# Sheet1.net
KiCad netlist of a schematic drawn in Altium Designer
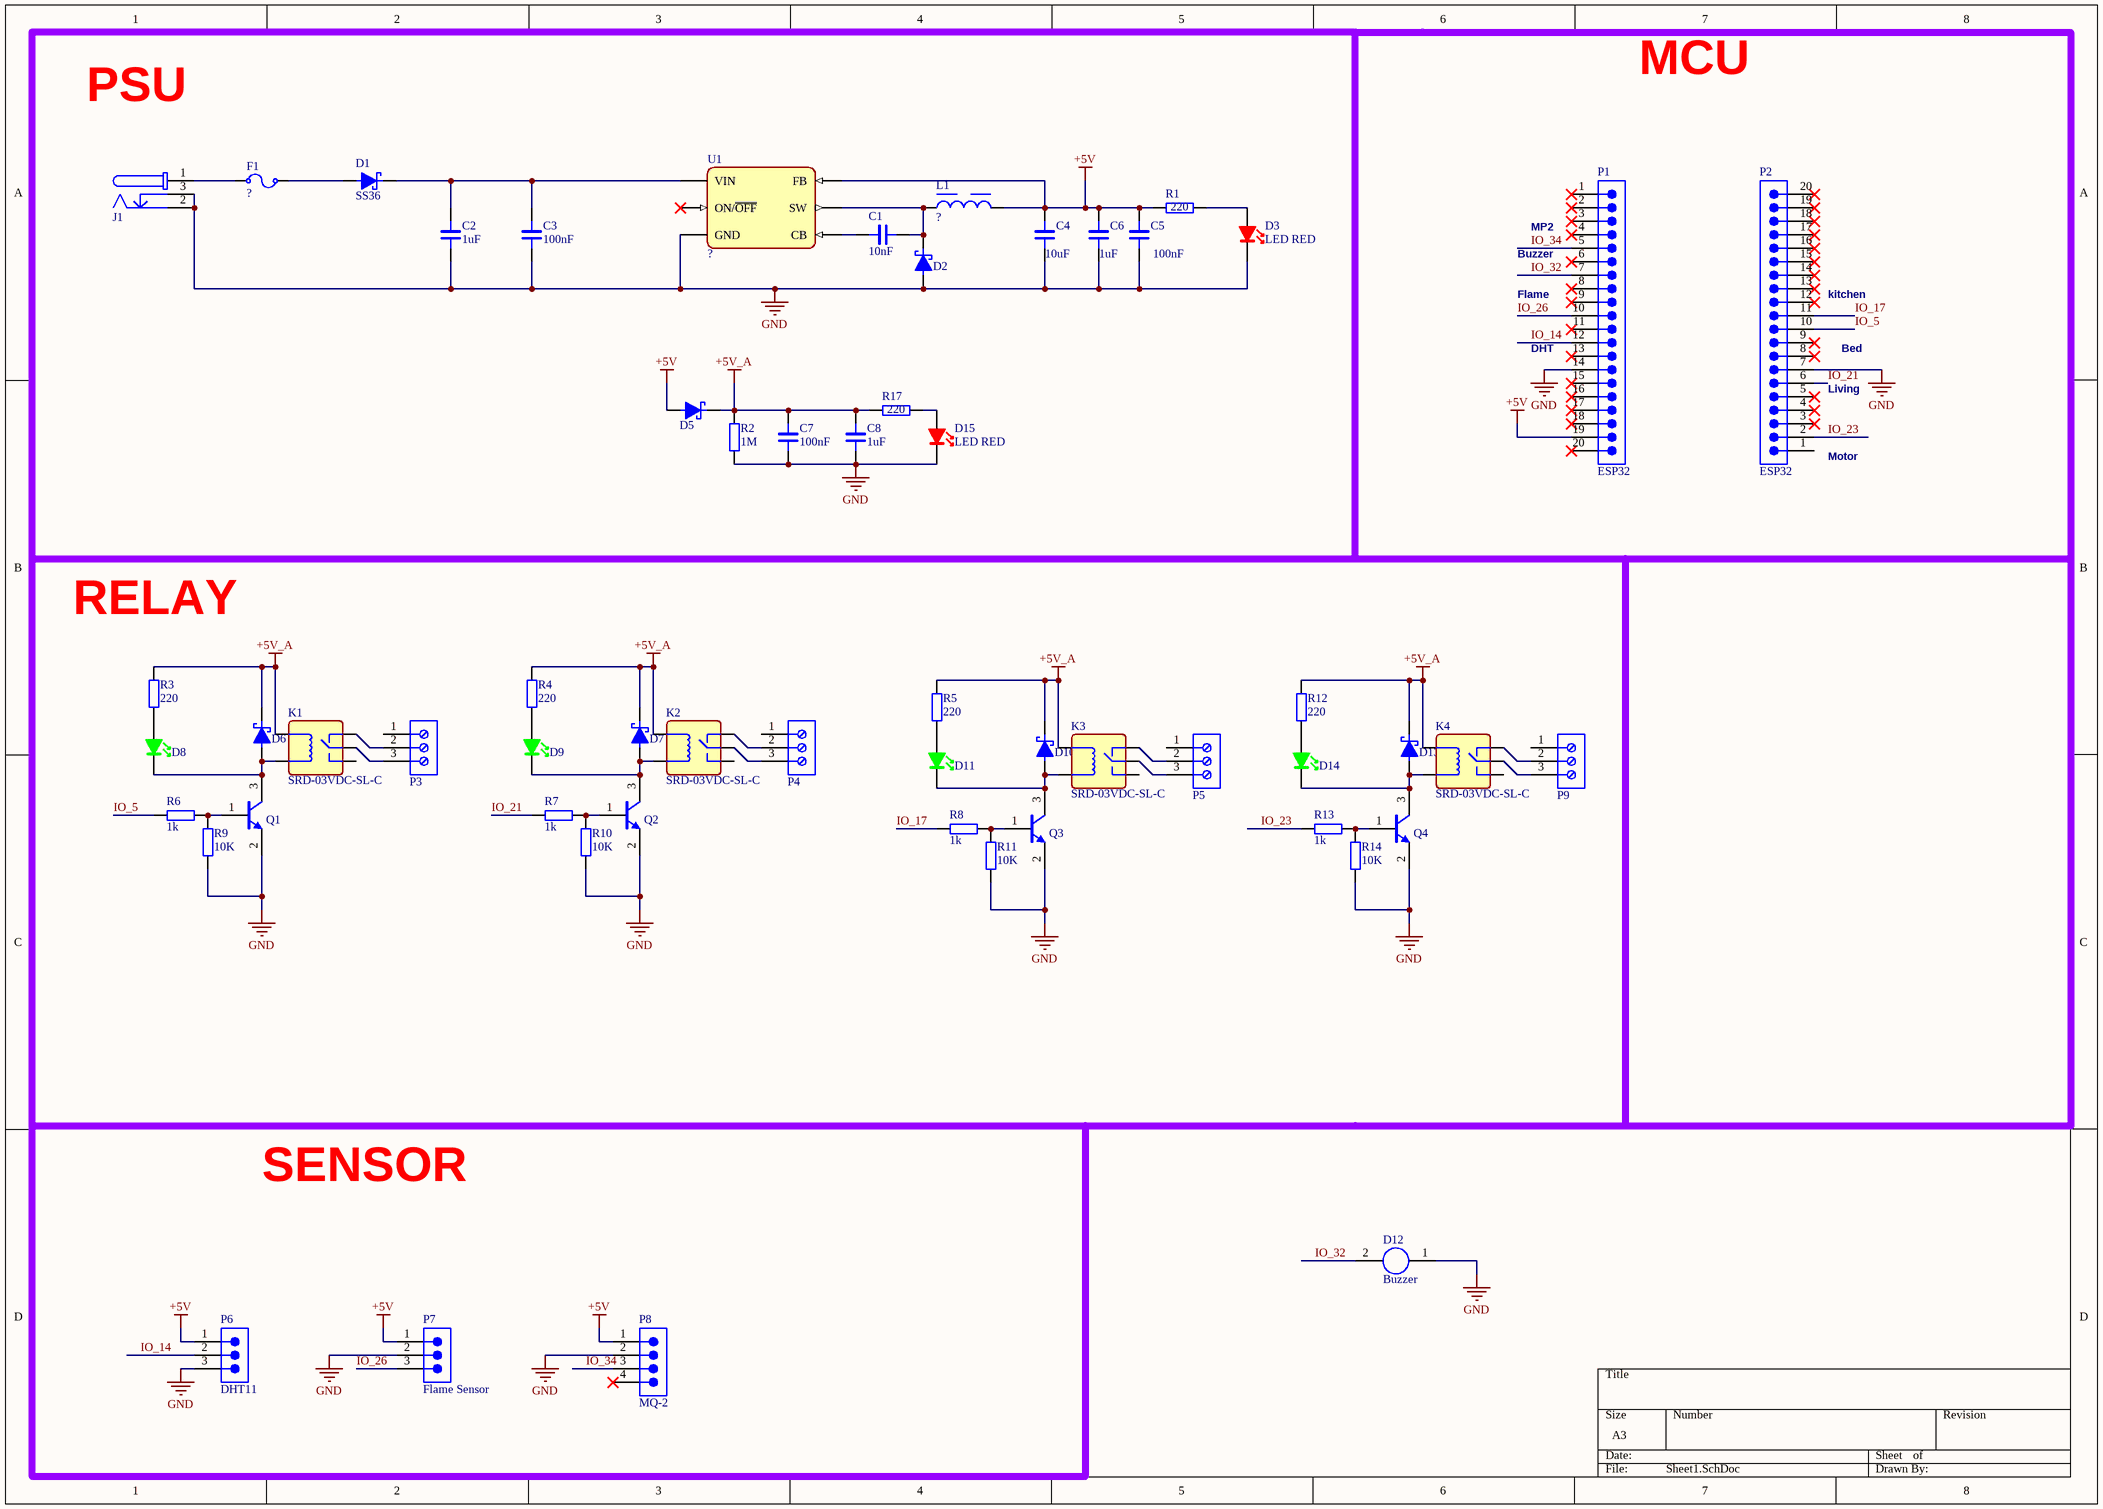
[diagram p0: Sheet1.SchDoc]

(export (version "E")
  (design (tool "Eeschema 10.0.6"))
  (components
    (comp (ref "C1")
      (value "10nF")
      (footprint "CAP_0805")
      (description "0805 Multilayer Ceramic Capacitors MLCC - SMD/SMT ROHS")
      (fields (field (name "LCSC PART") "?"))
      (libsource (lib "FIC_OAL") (part "CAP_0805"))
    )
    (comp (ref "C2")
      (value "1uF")
      (footprint "CAP_0805")
      (description "0805 Multilayer Ceramic Capacitors MLCC - SMD/SMT ROHS")
      (fields (field (name "LCSC PART") "?"))
      (libsource (lib "FIC_OAL") (part "CAP_0805"))
    )
    (comp (ref "C3")
      (value "100nF")
      (footprint "CAP_0805")
      (description "0805 Multilayer Ceramic Capacitors MLCC - SMD/SMT ROHS")
      (fields (field (name "LCSC PART") "?"))
      (libsource (lib "FIC_OAL") (part "CAP_0805"))
    )
    (comp (ref "C4")
      (value "10uF")
      (footprint "CAP_0805")
      (description "0805 Multilayer Ceramic Capacitors MLCC - SMD/SMT ROHS")
      (fields (field (name "LCSC PART") "?"))
      (libsource (lib "FIC_OAL") (part "CAP_0805"))
    )
    (comp (ref "C5")
      (value "100nF")
      (footprint "CAP_0805")
      (description "0805 Multilayer Ceramic Capacitors MLCC - SMD/SMT ROHS")
      (fields (field (name "LCSC PART") "?"))
      (libsource (lib "FIC_OAL") (part "CAP_0805"))
    )
    (comp (ref "C6")
      (value "1uF")
      (footprint "CAP_0805")
      (description "0805 Multilayer Ceramic Capacitors MLCC - SMD/SMT ROHS")
      (fields (field (name "LCSC PART") "?"))
      (libsource (lib "FIC_OAL") (part "CAP_0805"))
    )
    (comp (ref "C7")
      (value "100nF")
      (footprint "CAP_0805")
      (description "0805 Multilayer Ceramic Capacitors MLCC - SMD/SMT ROHS")
      (fields (field (name "LCSC PART") "?"))
      (libsource (lib "FIC_OAL") (part "CAP_0805"))
    )
    (comp (ref "C8")
      (value "1uF")
      (footprint "CAP_0805")
      (description "0805 Multilayer Ceramic Capacitors MLCC - SMD/SMT ROHS")
      (fields (field (name "LCSC PART") "?"))
      (libsource (lib "FIC_OAL") (part "CAP_0805"))
    )
    (comp (ref "D1")
      (value "SS36")
      (footprint "DIO_SMB")
      (description "60V 3A 700mV@3A SMB Schottky Barrier Diodes")
      (fields (field (name "MRF. PART") "?"))
      (libsource (lib "FIC_OAL") (part "DIO_SS36"))
    )
    (comp (ref "D2")
      (value "SS34")
      (footprint "DIO-SMA")
      (description "40V 500mV@3A 3A SMC (SBD)")
      (fields (field (name "MFR. PART") "?"))
      (libsource (lib "EOAL") (part "DIO-SS34"))
    )
    (comp (ref "D3")
      (value "LED RED")
      (footprint "LED_RED_V0805")
      (description "20mA 615nm~630nm RED")
      (fields (field (name "JLCPCB PART") "?"))
      (libsource (lib "FIC_OAL") (part "LED_RED_V0805"))
    )
    (comp (ref "D5")
      (value "SS34")
      (footprint "DIO_SMA")
      (description "40V 500mV@3A 3A SMC (SBD)")
      (fields (field (name "MFR. PART") "?"))
      (libsource (lib "FIC_OAL") (part "DIO_SS34"))
    )
    (comp (ref "D6")
      (value "SS34")
      (footprint "DIO_SMA")
      (description "40V 500mV@3A 3A SMC (SBD)")
      (fields (field (name "MFR. PART") "?"))
      (libsource (lib "FIC_OAL") (part "DIO_SS34"))
    )
    (comp (ref "D7")
      (value "SS34")
      (footprint "DIO_SMA")
      (description "40V 500mV@3A 3A SMC (SBD)")
      (fields (field (name "MFR. PART") "?"))
      (libsource (lib "FIC_OAL") (part "DIO_SS34"))
    )
    (comp (ref "D8")
      (value "GREEN LED")
      (footprint "LED_GREEN_V0805")
      (description "20mA 615nm~630nm GREEN")
      (fields (field (name "JLCPCB PART") "?"))
      (libsource (lib "FIC_OAL") (part "LED_GREEN_V0805"))
    )
    (comp (ref "D9")
      (value "GREEN LED")
      (footprint "LED_GREEN_V0805")
      (description "20mA 615nm~630nm GREEN")
      (fields (field (name "JLCPCB PART") "?"))
      (libsource (lib "FIC_OAL") (part "LED_GREEN_V0805"))
    )
    (comp (ref "D10")
      (value "SS34")
      (footprint "DIO_SMA")
      (description "40V 500mV@3A 3A SMC (SBD)")
      (fields (field (name "MFR. PART") "?"))
      (libsource (lib "FIC_OAL") (part "DIO_SS34"))
    )
    (comp (ref "D11")
      (value "GREEN LED")
      (footprint "LED_GREEN_V0805")
      (description "20mA 615nm~630nm GREEN")
      (fields (field (name "JLCPCB PART") "?"))
      (libsource (lib "FIC_OAL") (part "LED_GREEN_V0805"))
    )
    (comp (ref "D12")
      (value "Buzzer")
      (footprint "PCBComponent_1")
      (libsource (lib "Integrated_Library1") (part "Component_1"))
    )
    (comp (ref "D13")
      (value "SS34")
      (footprint "DIO_SMA")
      (description "40V 500mV@3A 3A SMC (SBD)")
      (fields (field (name "MFR. PART") "?"))
      (libsource (lib "FIC_OAL") (part "DIO_SS34"))
    )
    (comp (ref "D14")
      (value "GREEN LED")
      (footprint "LED_GREEN_V0805")
      (description "20mA 615nm~630nm GREEN")
      (fields (field (name "JLCPCB PART") "?"))
      (libsource (lib "FIC_OAL") (part "LED_GREEN_V0805"))
    )
    (comp (ref "D15")
      (value "LED RED")
      (footprint "LED_RED_V0805")
      (description "20mA 615nm~630nm RED")
      (fields (field (name "JLCPCB PART") "?"))
      (libsource (lib "FIC_OAL") (part "LED_RED_V0805"))
    )
    (comp (ref "F1")
      (value "?")
      (footprint "FUS_PPTC0805")
      (description "0805 Resettable Fuses")
      (libsource (lib "EOAL") (part "FUS-PPTC0805"))
    )
    (comp (ref "J1")
      (value "JACK-Power-DC5.5mm")
      (footprint "CON-JACK-PWR-DC550")
      (description "DC Power Jack Right Angled THT 5.5mmx2.1mm")
      (fields (field (name "MRF. PART") "?"))
      (libsource (lib "FIC_OAL") (part "CON-JACK-PWR-DC550"))
    )
    (comp (ref "K1")
      (value "SRD-03VDC-SL-C")
      (footprint "RLY")
      (libsource (lib "Integrated_Library1") (part "RLY"))
    )
    (comp (ref "K2")
      (value "SRD-03VDC-SL-C")
      (footprint "RLY")
      (libsource (lib "Integrated_Library1") (part "RLY"))
    )
    (comp (ref "K3")
      (value "SRD-03VDC-SL-C")
      (footprint "RLY")
      (libsource (lib "Integrated_Library1") (part "RLY"))
    )
    (comp (ref "K4")
      (value "SRD-03VDC-SL-C")
      (footprint "RLY")
      (libsource (lib "Integrated_Library1") (part "RLY"))
    )
    (comp (ref "L1")
      (value "?")
      (footprint "INDM_7366")
      (description "(7.30mmx6.60mm) Shielded Molded Inductor")
      (libsource (lib "EOAL") (part "INDM_7366"))
    )
    (comp (ref "P1")
      (value "ESP32")
      (footprint "61302011121")
      (libsource (lib "Altium Content Vault") (part "Header_Male_1R_20P"))
    )
    (comp (ref "P2")
      (value "ESP32")
      (footprint "61302011121")
      (libsource (lib "Altium Content Vault") (part "Header_Male_1R_20P"))
    )
    (comp (ref "P3")
      (value "Terminal Block")
      (footprint "CON_03_508_STBRC")
      (description "5.08 mm Horizontal Entry Modular w. Rising Cage Clamp")
      (fields (field (name "MFR. PART") "?"))
      (libsource (lib "FIC_OAL") (part "CON_03_508_STBRC"))
    )
    (comp (ref "P4")
      (value "Terminal Block")
      (footprint "CON_03_508_STBRC")
      (description "5.08 mm Horizontal Entry Modular w. Rising Cage Clamp")
      (fields (field (name "MFR. PART") "?"))
      (libsource (lib "FIC_OAL") (part "CON_03_508_STBRC"))
    )
    (comp (ref "P5")
      (value "Terminal Block")
      (footprint "CON_03_508_STBRC")
      (description "5.08 mm Horizontal Entry Modular w. Rising Cage Clamp")
      (fields (field (name "MFR. PART") "?"))
      (libsource (lib "FIC_OAL") (part "CON_03_508_STBRC"))
    )
    (comp (ref "P6")
      (value "DHT11")
      (footprint "CON -PHD-03254-VSM")
      (description "3P 2.54mm Vertical Pin Header")
      (fields (field (name "MRF. PART") "?"))
      (libsource (lib "FIC_OAL") (part "CON -PHD-03254-VSM"))
    )
    (comp (ref "P7")
      (value "Flame Sensor")
      (footprint "CON -PHD-03254-VSM")
      (description "3P 2.54mm Vertical Pin Header")
      (fields (field (name "MRF. PART") "?"))
      (libsource (lib "FIC_OAL") (part "CON -PHD-03254-VSM"))
    )
    (comp (ref "P8")
      (value "MQ-2")
      (footprint "CON_04_254_VSMBHD")
      (description "2.54mm 4P Male Vertical Shrouded Header")
      (fields (field (name "MRF. PART") "?"))
      (libsource (lib "FIC_OAL") (part "CON_04_254_VSMBHD"))
    )
    (comp (ref "P9")
      (value "Terminal Block")
      (footprint "CON_03_508_STBRC")
      (description "5.08 mm Horizontal Entry Modular w. Rising Cage Clamp")
      (fields (field (name "MFR. PART") "?"))
      (libsource (lib "FIC_OAL") (part "CON_03_508_STBRC"))
    )
    (comp (ref "Q1")
      (value "BC846x")
      (footprint "BJT_ BC846x")
      (description "Single Bipolar Transistor, NPN, 65 V, 100 mA, 250 mW, SOT23 (TO-236AB), 3 Pins, Surface Mount")
      (fields (field (name "MRF. PART") "?"))
      (libsource (lib "FIC_OAL") (part "BJT_ BC846x"))
    )
    (comp (ref "Q2")
      (value "BC846x")
      (footprint "BJT_ BC846x")
      (description "Single Bipolar Transistor, NPN, 65 V, 100 mA, 250 mW, SOT23 (TO-236AB), 3 Pins, Surface Mount")
      (fields (field (name "MRF. PART") "?"))
      (libsource (lib "FIC_OAL") (part "BJT_ BC846x"))
    )
    (comp (ref "Q3")
      (value "BC846x")
      (footprint "BJT_ BC846x")
      (description "Single Bipolar Transistor, NPN, 65 V, 100 mA, 250 mW, SOT23 (TO-236AB), 3 Pins, Surface Mount")
      (fields (field (name "MRF. PART") "?"))
      (libsource (lib "FIC_OAL") (part "BJT_ BC846x"))
    )
    (comp (ref "Q4")
      (value "BC846x")
      (footprint "BJT_ BC846x")
      (description "Single Bipolar Transistor, NPN, 65 V, 100 mA, 250 mW, SOT23 (TO-236AB), 3 Pins, Surface Mount")
      (fields (field (name "MRF. PART") "?"))
      (libsource (lib "FIC_OAL") (part "BJT_ BC846x"))
    )
    (comp (ref "R1")
      (value "220")
      (footprint "RES_0805")
      (description "0805 Thick Film Resistor - Surface Mount ROHS")
      (fields (field (name "MFR. PART") "?"))
      (libsource (lib "FIC_OAL") (part "RES_0805"))
    )
    (comp (ref "R2")
      (value "1M")
      (footprint "RES_0805")
      (description "0805 Thick Film Resistor - Surface Mount ROHS")
      (fields (field (name "MFR. PART") "?"))
      (libsource (lib "FIC_OAL") (part "RES_0805"))
    )
    (comp (ref "R3")
      (value "220")
      (footprint "RES_0805")
      (description "0805 Thick Film Resistor - Surface Mount ROHS")
      (fields (field (name "MFR. PART") "?"))
      (libsource (lib "FIC_OAL") (part "RES_0805"))
    )
    (comp (ref "R4")
      (value "220")
      (footprint "RES_0805")
      (description "0805 Thick Film Resistor - Surface Mount ROHS")
      (fields (field (name "MFR. PART") "?"))
      (libsource (lib "FIC_OAL") (part "RES_0805"))
    )
    (comp (ref "R5")
      (value "220")
      (footprint "RES_0805")
      (description "0805 Thick Film Resistor - Surface Mount ROHS")
      (fields (field (name "MFR. PART") "?"))
      (libsource (lib "FIC_OAL") (part "RES_0805"))
    )
    (comp (ref "R6")
      (value "1k")
      (footprint "RES_0805")
      (description "0805 Thick Film Resistor - Surface Mount ROHS")
      (fields (field (name "MFR. PART") "?"))
      (libsource (lib "FIC_OAL") (part "RES_0805"))
    )
    (comp (ref "R7")
      (value "1k")
      (footprint "RES_0805")
      (description "0805 Thick Film Resistor - Surface Mount ROHS")
      (fields (field (name "MFR. PART") "?"))
      (libsource (lib "FIC_OAL") (part "RES_0805"))
    )
    (comp (ref "R8")
      (value "1k")
      (footprint "RES_0805")
      (description "0805 Thick Film Resistor - Surface Mount ROHS")
      (fields (field (name "MFR. PART") "?"))
      (libsource (lib "FIC_OAL") (part "RES_0805"))
    )
    (comp (ref "R9")
      (value "10K")
      (footprint "RES_0805")
      (description "0805 Thick Film Resistor - Surface Mount ROHS")
      (fields (field (name "MFR. PART") "?"))
      (libsource (lib "FIC_OAL") (part "RES_0805"))
    )
    (comp (ref "R10")
      (value "10K")
      (footprint "RES_0805")
      (description "0805 Thick Film Resistor - Surface Mount ROHS")
      (fields (field (name "MFR. PART") "?"))
      (libsource (lib "FIC_OAL") (part "RES_0805"))
    )
    (comp (ref "R11")
      (value "10K")
      (footprint "RES_0805")
      (description "0805 Thick Film Resistor - Surface Mount ROHS")
      (fields (field (name "MFR. PART") "?"))
      (libsource (lib "FIC_OAL") (part "RES_0805"))
    )
    (comp (ref "R12")
      (value "220")
      (footprint "RES_0805")
      (description "0805 Thick Film Resistor - Surface Mount ROHS")
      (fields (field (name "MFR. PART") "?"))
      (libsource (lib "FIC_OAL") (part "RES_0805"))
    )
    (comp (ref "R13")
      (value "1k")
      (footprint "RES_0805")
      (description "0805 Thick Film Resistor - Surface Mount ROHS")
      (fields (field (name "MFR. PART") "?"))
      (libsource (lib "FIC_OAL") (part "RES_0805"))
    )
    (comp (ref "R14")
      (value "10K")
      (footprint "RES_0805")
      (description "0805 Thick Film Resistor - Surface Mount ROHS")
      (fields (field (name "MFR. PART") "?"))
      (libsource (lib "FIC_OAL") (part "RES_0805"))
    )
    (comp (ref "R17")
      (value "220")
      (footprint "RES_0805")
      (description "0805 Thick Film Resistor - Surface Mount ROHS")
      (fields (field (name "MFR. PART") "?"))
      (libsource (lib "FIC_OAL") (part "RES_0805"))
    )
    (comp (ref "U1")
      (value "?")
      (footprint "LM2675MX")
      (description "Buck Converter, 6.5V-40V-3A, 8-Pin SOIC")
      (fields (field (name "MFR. PART") "LM2675MX"))
      (libsource (lib "EOAL") (part "LM2675MX"))
    )
  )
  (nets
    (net (code "1") (name "+5V") (class "Default")
      (node (ref "C4") (pin "2") (pinfunction "2_2") (pintype "passive"))
      (node (ref "C5") (pin "2") (pinfunction "2_2") (pintype "passive"))
      (node (ref "C6") (pin "2") (pinfunction "2_2") (pintype "passive"))
      (node (ref "D5") (pin "A") (pinfunction "A_A") (pintype "passive"))
      (node (ref "L1") (pin "2") (pinfunction "2_2") (pintype "passive"))
      (node (ref "P1") (pin "19") (pinfunction "19_19") (pintype "passive"))
      (node (ref "P6") (pin "1") (pinfunction "1_1") (pintype "passive"))
      (node (ref "P7") (pin "1") (pinfunction "1_1") (pintype "passive"))
      (node (ref "P8") (pin "1") (pinfunction "1_1") (pintype "passive"))
      (node (ref "R1") (pin "1") (pinfunction "1_1") (pintype "passive"))
      (node (ref "U1") (pin "4") (pinfunction "FB_4") (pintype "input"))
    )
    (net (code "2") (name "+5V_A") (class "Default")
      (node (ref "C7") (pin "2") (pinfunction "2_2") (pintype "passive"))
      (node (ref "C8") (pin "2") (pinfunction "2_2") (pintype "passive"))
      (node (ref "D10") (pin "C") (pinfunction "C_C") (pintype "passive"))
      (node (ref "D13") (pin "C") (pinfunction "C_C") (pintype "passive"))
      (node (ref "D5") (pin "C") (pinfunction "C_C") (pintype "passive"))
      (node (ref "D6") (pin "C") (pinfunction "C_C") (pintype "passive"))
      (node (ref "D7") (pin "C") (pinfunction "C_C") (pintype "passive"))
      (node (ref "K1") (pin "4") (pinfunction "4_4") (pintype "passive"))
      (node (ref "K2") (pin "4") (pinfunction "4_4") (pintype "passive"))
      (node (ref "K3") (pin "4") (pinfunction "4_4") (pintype "passive"))
      (node (ref "K4") (pin "4") (pinfunction "4_4") (pintype "passive"))
      (node (ref "R12") (pin "2") (pinfunction "2_2") (pintype "passive"))
      (node (ref "R17") (pin "1") (pinfunction "1_1") (pintype "passive"))
      (node (ref "R2") (pin "1") (pinfunction "1_1") (pintype "passive"))
      (node (ref "R3") (pin "2") (pinfunction "2_2") (pintype "passive"))
      (node (ref "R4") (pin "2") (pinfunction "2_2") (pintype "passive"))
      (node (ref "R5") (pin "2") (pinfunction "2_2") (pintype "passive"))
    )
    (net (code "3") (name "/IO_5") (class "Default")
      (node (ref "P2") (pin "10") (pinfunction "10_10") (pintype "passive"))
      (node (ref "R6") (pin "2") (pinfunction "2_2") (pintype "passive"))
    )
    (net (code "4") (name "/IO_14") (class "Default")
      (node (ref "P1") (pin "12") (pinfunction "12_12") (pintype "passive"))
      (node (ref "P6") (pin "2") (pinfunction "2_2") (pintype "passive"))
    )
    (net (code "5") (name "/IO_17") (class "Default")
      (node (ref "P2") (pin "11") (pinfunction "11_11") (pintype "passive"))
      (node (ref "R8") (pin "2") (pinfunction "2_2") (pintype "passive"))
    )
    (net (code "6") (name "/IO_21") (class "Default")
      (node (ref "P2") (pin "6") (pinfunction "6_6") (pintype "passive"))
      (node (ref "R7") (pin "2") (pinfunction "2_2") (pintype "passive"))
    )
    (net (code "7") (name "/IO_23") (class "Default")
      (node (ref "P2") (pin "2") (pinfunction "2_2") (pintype "passive"))
      (node (ref "R13") (pin "2") (pinfunction "2_2") (pintype "passive"))
    )
    (net (code "8") (name "/IO_26") (class "Default")
      (node (ref "P1") (pin "10") (pinfunction "10_10") (pintype "passive"))
      (node (ref "P7") (pin "3") (pinfunction "3_3") (pintype "passive"))
    )
    (net (code "9") (name "/IO_32") (class "Default")
      (node (ref "D12") (pin "2") (pinfunction "2_2") (pintype "passive"))
      (node (ref "P1") (pin "7") (pinfunction "7_7") (pintype "passive"))
    )
    (net (code "10") (name "/IO_34") (class "Default")
      (node (ref "P1") (pin "5") (pinfunction "5_5") (pintype "passive"))
      (node (ref "P8") (pin "3") (pinfunction "3_3") (pintype "passive"))
    )
    (net (code "11") (name "GND") (class "Default")
      (node (ref "C2") (pin "1") (pinfunction "1_1") (pintype "passive"))
      (node (ref "C3") (pin "1") (pinfunction "1_1") (pintype "passive"))
      (node (ref "C4") (pin "1") (pinfunction "1_1") (pintype "passive"))
      (node (ref "C5") (pin "1") (pinfunction "1_1") (pintype "passive"))
      (node (ref "C6") (pin "1") (pinfunction "1_1") (pintype "passive"))
      (node (ref "C7") (pin "1") (pinfunction "1_1") (pintype "passive"))
      (node (ref "C8") (pin "1") (pinfunction "1_1") (pintype "passive"))
      (node (ref "D12") (pin "1") (pinfunction "1_1") (pintype "passive"))
      (node (ref "D15") (pin "C") (pinfunction "1_C") (pintype "passive"))
      (node (ref "D2") (pin "A") (pinfunction "A_A") (pintype "passive"))
      (node (ref "D3") (pin "C") (pinfunction "1_C") (pintype "passive"))
      (node (ref "J1") (pin "2") (pinfunction "2_2") (pintype "passive"))
      (node (ref "J1") (pin "3") (pinfunction "3_3") (pintype "passive"))
      (node (ref "P1") (pin "14") (pinfunction "14_14") (pintype "passive"))
      (node (ref "P2") (pin "7") (pinfunction "7_7") (pintype "passive"))
      (node (ref "P6") (pin "3") (pinfunction "3_3") (pintype "passive"))
      (node (ref "P7") (pin "2") (pinfunction "2_2") (pintype "passive"))
      (node (ref "P8") (pin "2") (pinfunction "2_2") (pintype "passive"))
      (node (ref "Q1") (pin "2") (pinfunction "E_2") (pintype "passive"))
      (node (ref "Q2") (pin "2") (pinfunction "E_2") (pintype "passive"))
      (node (ref "Q3") (pin "2") (pinfunction "E_2") (pintype "passive"))
      (node (ref "Q4") (pin "2") (pinfunction "E_2") (pintype "passive"))
      (node (ref "R10") (pin "2") (pinfunction "2_2") (pintype "passive"))
      (node (ref "R11") (pin "2") (pinfunction "2_2") (pintype "passive"))
      (node (ref "R14") (pin "2") (pinfunction "2_2") (pintype "passive"))
      (node (ref "R2") (pin "2") (pinfunction "2_2") (pintype "passive"))
      (node (ref "R9") (pin "2") (pinfunction "2_2") (pintype "passive"))
      (node (ref "U1") (pin "6") (pinfunction "GND_6") (pintype "passive"))
    )
    (net (code "12") (name "Net-(D1-PadA)") (class "Default")
      (node (ref "D1") (pin "A") (pinfunction "A_A") (pintype "passive"))
      (node (ref "F1") (pin "1") (pinfunction "1_1") (pintype "passive"))
    )
    (net (code "13") (name "Net-(D3-2)") (class "Default")
      (node (ref "D3") (pin "A") (pinfunction "2_A") (pintype "passive"))
      (node (ref "R1") (pin "2") (pinfunction "2_2") (pintype "passive"))
    )
    (net (code "14") (name "Net-(D8-1)") (class "Default")
      (node (ref "D6") (pin "A") (pinfunction "A_A") (pintype "passive"))
      (node (ref "D8") (pin "C") (pinfunction "1_C") (pintype "passive"))
      (node (ref "K1") (pin "1") (pinfunction "1_1") (pintype "passive"))
      (node (ref "Q1") (pin "3") (pinfunction "C_3") (pintype "passive"))
    )
    (net (code "15") (name "Net-(D8-2)") (class "Default")
      (node (ref "D8") (pin "A") (pinfunction "2_A") (pintype "passive"))
      (node (ref "R3") (pin "1") (pinfunction "1_1") (pintype "passive"))
    )
    (net (code "16") (name "Net-(D9-1)") (class "Default")
      (node (ref "D7") (pin "A") (pinfunction "A_A") (pintype "passive"))
      (node (ref "D9") (pin "C") (pinfunction "1_C") (pintype "passive"))
      (node (ref "K2") (pin "1") (pinfunction "1_1") (pintype "passive"))
      (node (ref "Q2") (pin "3") (pinfunction "C_3") (pintype "passive"))
    )
    (net (code "17") (name "Net-(D9-2)") (class "Default")
      (node (ref "D9") (pin "A") (pinfunction "2_A") (pintype "passive"))
      (node (ref "R4") (pin "1") (pinfunction "1_1") (pintype "passive"))
    )
    (net (code "18") (name "Net-(D11-1)") (class "Default")
      (node (ref "D10") (pin "A") (pinfunction "A_A") (pintype "passive"))
      (node (ref "D11") (pin "C") (pinfunction "1_C") (pintype "passive"))
      (node (ref "K3") (pin "1") (pinfunction "1_1") (pintype "passive"))
      (node (ref "Q3") (pin "3") (pinfunction "C_3") (pintype "passive"))
    )
    (net (code "19") (name "Net-(D11-2)") (class "Default")
      (node (ref "D11") (pin "A") (pinfunction "2_A") (pintype "passive"))
      (node (ref "R5") (pin "1") (pinfunction "1_1") (pintype "passive"))
    )
    (net (code "20") (name "Net-(D14-1)") (class "Default")
      (node (ref "D13") (pin "A") (pinfunction "A_A") (pintype "passive"))
      (node (ref "D14") (pin "C") (pinfunction "1_C") (pintype "passive"))
      (node (ref "K4") (pin "1") (pinfunction "1_1") (pintype "passive"))
      (node (ref "Q4") (pin "3") (pinfunction "C_3") (pintype "passive"))
    )
    (net (code "21") (name "Net-(D14-2)") (class "Default")
      (node (ref "D14") (pin "A") (pinfunction "2_A") (pintype "passive"))
      (node (ref "R12") (pin "1") (pinfunction "1_1") (pintype "passive"))
    )
    (net (code "22") (name "Net-(D15-2)") (class "Default")
      (node (ref "D15") (pin "A") (pinfunction "2_A") (pintype "passive"))
      (node (ref "R17") (pin "2") (pinfunction "2_2") (pintype "passive"))
    )
    (net (code "23") (name "Net-(F1-Pad1)") (class "Default")
      (node (ref "F1") (pin "1") (pinfunction "1_1") (pintype "passive"))
      (node (ref "J1") (pin "1") (pinfunction "1_1") (pintype "passive"))
    )
    (net (code "24") (name "Net-(K1-Pad3)") (class "Default")
      (node (ref "K1") (pin "3") (pinfunction "3_3") (pintype "passive"))
      (node (ref "P3") (pin "3") (pinfunction "3_3") (pintype "passive"))
    )
    (net (code "25") (name "Net-(K1-Pad5)") (class "Default")
      (node (ref "K1") (pin "5") (pinfunction "5_5") (pintype "passive"))
      (node (ref "P3") (pin "2") (pinfunction "2_2") (pintype "passive"))
    )
    (net (code "26") (name "Net-(K2-Pad3)") (class "Default")
      (node (ref "K2") (pin "3") (pinfunction "3_3") (pintype "passive"))
      (node (ref "P4") (pin "3") (pinfunction "3_3") (pintype "passive"))
    )
    (net (code "27") (name "Net-(K2-Pad5)") (class "Default")
      (node (ref "K2") (pin "5") (pinfunction "5_5") (pintype "passive"))
      (node (ref "P4") (pin "2") (pinfunction "2_2") (pintype "passive"))
    )
    (net (code "28") (name "Net-(K3-Pad3)") (class "Default")
      (node (ref "K3") (pin "3") (pinfunction "3_3") (pintype "passive"))
      (node (ref "P5") (pin "3") (pinfunction "3_3") (pintype "passive"))
    )
    (net (code "29") (name "Net-(K3-Pad5)") (class "Default")
      (node (ref "K3") (pin "5") (pinfunction "5_5") (pintype "passive"))
      (node (ref "P5") (pin "2") (pinfunction "2_2") (pintype "passive"))
    )
    (net (code "30") (name "Net-(K4-Pad3)") (class "Default")
      (node (ref "K4") (pin "3") (pinfunction "3_3") (pintype "passive"))
      (node (ref "P9") (pin "3") (pinfunction "3_3") (pintype "passive"))
    )
    (net (code "31") (name "Net-(K4-Pad5)") (class "Default")
      (node (ref "K4") (pin "5") (pinfunction "5_5") (pintype "passive"))
      (node (ref "P9") (pin "2") (pinfunction "2_2") (pintype "passive"))
    )
    (net (code "32") (name "Net-(Q1-B)") (class "Default")
      (node (ref "Q1") (pin "1") (pinfunction "B_1") (pintype "passive"))
      (node (ref "R6") (pin "1") (pinfunction "1_1") (pintype "passive"))
      (node (ref "R9") (pin "1") (pinfunction "1_1") (pintype "passive"))
    )
    (net (code "33") (name "Net-(Q2-B)") (class "Default")
      (node (ref "Q2") (pin "1") (pinfunction "B_1") (pintype "passive"))
      (node (ref "R10") (pin "1") (pinfunction "1_1") (pintype "passive"))
      (node (ref "R7") (pin "1") (pinfunction "1_1") (pintype "passive"))
    )
    (net (code "34") (name "Net-(Q3-B)") (class "Default")
      (node (ref "Q3") (pin "1") (pinfunction "B_1") (pintype "passive"))
      (node (ref "R11") (pin "1") (pinfunction "1_1") (pintype "passive"))
      (node (ref "R8") (pin "1") (pinfunction "1_1") (pintype "passive"))
    )
    (net (code "35") (name "Net-(Q4-B)") (class "Default")
      (node (ref "Q4") (pin "1") (pinfunction "B_1") (pintype "passive"))
      (node (ref "R13") (pin "1") (pinfunction "1_1") (pintype "passive"))
      (node (ref "R14") (pin "1") (pinfunction "1_1") (pintype "passive"))
    )
    (net (code "36") (name "Net-(U1-CB)") (class "Default")
      (node (ref "C1") (pin "1") (pinfunction "1_1") (pintype "passive"))
      (node (ref "U1") (pin "1") (pinfunction "CB_1") (pintype "input"))
    )
    (net (code "37") (name "Net-(U1-SW)") (class "Default")
      (node (ref "C1") (pin "2") (pinfunction "2_2") (pintype "passive"))
      (node (ref "D2") (pin "C") (pinfunction "C_C") (pintype "passive"))
      (node (ref "L1") (pin "1") (pinfunction "1_1") (pintype "passive"))
      (node (ref "U1") (pin "8") (pinfunction "SW_8") (pintype "output"))
    )
    (net (code "38") (name "Net-(U1-VIN)") (class "Default")
      (node (ref "C2") (pin "2") (pinfunction "2_2") (pintype "passive"))
      (node (ref "C3") (pin "2") (pinfunction "2_2") (pintype "passive"))
      (node (ref "D1") (pin "C") (pinfunction "C_C") (pintype "passive"))
      (node (ref "U1") (pin "7") (pinfunction "VIN_7") (pintype "passive"))
    )
    (net (code "39") (name "unconnected-(K1-Pad2)") (class "Default")
      (node (ref "K1") (pin "2") (pinfunction "2_2") (pintype "passive"))
    )
    (net (code "40") (name "unconnected-(K2-Pad2)") (class "Default")
      (node (ref "K2") (pin "2") (pinfunction "2_2") (pintype "passive"))
    )
    (net (code "41") (name "unconnected-(K3-Pad2)") (class "Default")
      (node (ref "K3") (pin "2") (pinfunction "2_2") (pintype "passive"))
    )
    (net (code "42") (name "unconnected-(K4-Pad2)") (class "Default")
      (node (ref "K4") (pin "2") (pinfunction "2_2") (pintype "passive"))
    )
    (net (code "43") (name "unconnected-(P1-Pad1)") (class "Default")
      (node (ref "P1") (pin "1") (pinfunction "1_1") (pintype "passive+no_connect"))
    )
    (net (code "44") (name "unconnected-(P1-Pad2)") (class "Default")
      (node (ref "P1") (pin "2") (pinfunction "2_2") (pintype "passive+no_connect"))
    )
    (net (code "45") (name "unconnected-(P1-Pad3)") (class "Default")
      (node (ref "P1") (pin "3") (pinfunction "3_3") (pintype "passive+no_connect"))
    )
    (net (code "46") (name "unconnected-(P1-Pad4)") (class "Default")
      (node (ref "P1") (pin "4") (pinfunction "4_4") (pintype "passive+no_connect"))
    )
    (net (code "47") (name "unconnected-(P1-Pad6)") (class "Default")
      (node (ref "P1") (pin "6") (pinfunction "6_6") (pintype "passive+no_connect"))
    )
    (net (code "48") (name "unconnected-(P1-Pad8)") (class "Default")
      (node (ref "P1") (pin "8") (pinfunction "8_8") (pintype "passive+no_connect"))
    )
    (net (code "49") (name "unconnected-(P1-Pad9)") (class "Default")
      (node (ref "P1") (pin "9") (pinfunction "9_9") (pintype "passive+no_connect"))
    )
    (net (code "50") (name "unconnected-(P1-Pad11)") (class "Default")
      (node (ref "P1") (pin "11") (pinfunction "11_11") (pintype "passive+no_connect"))
    )
    (net (code "51") (name "unconnected-(P1-Pad13)") (class "Default")
      (node (ref "P1") (pin "13") (pinfunction "13_13") (pintype "passive+no_connect"))
    )
    (net (code "52") (name "unconnected-(P1-Pad15)") (class "Default")
      (node (ref "P1") (pin "15") (pinfunction "15_15") (pintype "passive+no_connect"))
    )
    (net (code "53") (name "unconnected-(P1-Pad16)") (class "Default")
      (node (ref "P1") (pin "16") (pinfunction "16_16") (pintype "passive+no_connect"))
    )
    (net (code "54") (name "unconnected-(P1-Pad17)") (class "Default")
      (node (ref "P1") (pin "17") (pinfunction "17_17") (pintype "passive+no_connect"))
    )
    (net (code "55") (name "unconnected-(P1-Pad18)") (class "Default")
      (node (ref "P1") (pin "18") (pinfunction "18_18") (pintype "passive+no_connect"))
    )
    (net (code "56") (name "unconnected-(P1-Pad20)") (class "Default")
      (node (ref "P1") (pin "20") (pinfunction "20_20") (pintype "passive+no_connect"))
    )
    (net (code "57") (name "unconnected-(P2-Pad1)") (class "Default")
      (node (ref "P2") (pin "1") (pinfunction "1_1") (pintype "passive"))
    )
    (net (code "58") (name "unconnected-(P2-Pad3)") (class "Default")
      (node (ref "P2") (pin "3") (pinfunction "3_3") (pintype "passive+no_connect"))
    )
    (net (code "59") (name "unconnected-(P2-Pad4)") (class "Default")
      (node (ref "P2") (pin "4") (pinfunction "4_4") (pintype "passive+no_connect"))
    )
    (net (code "60") (name "unconnected-(P2-Pad5)") (class "Default")
      (node (ref "P2") (pin "5") (pinfunction "5_5") (pintype "passive+no_connect"))
    )
    (net (code "61") (name "unconnected-(P2-Pad8)") (class "Default")
      (node (ref "P2") (pin "8") (pinfunction "8_8") (pintype "passive+no_connect"))
    )
    (net (code "62") (name "unconnected-(P2-Pad9)") (class "Default")
      (node (ref "P2") (pin "9") (pinfunction "9_9") (pintype "passive+no_connect"))
    )
    (net (code "63") (name "unconnected-(P2-Pad12)") (class "Default")
      (node (ref "P2") (pin "12") (pinfunction "12_12") (pintype "passive+no_connect"))
    )
    (net (code "64") (name "unconnected-(P2-Pad13)") (class "Default")
      (node (ref "P2") (pin "13") (pinfunction "13_13") (pintype "passive+no_connect"))
    )
    (net (code "65") (name "unconnected-(P2-Pad14)") (class "Default")
      (node (ref "P2") (pin "14") (pinfunction "14_14") (pintype "passive+no_connect"))
    )
    (net (code "66") (name "unconnected-(P2-Pad15)") (class "Default")
      (node (ref "P2") (pin "15") (pinfunction "15_15") (pintype "passive+no_connect"))
    )
    (net (code "67") (name "unconnected-(P2-Pad16)") (class "Default")
      (node (ref "P2") (pin "16") (pinfunction "16_16") (pintype "passive+no_connect"))
    )
    (net (code "68") (name "unconnected-(P2-Pad17)") (class "Default")
      (node (ref "P2") (pin "17") (pinfunction "17_17") (pintype "passive+no_connect"))
    )
    (net (code "69") (name "unconnected-(P2-Pad18)") (class "Default")
      (node (ref "P2") (pin "18") (pinfunction "18_18") (pintype "passive+no_connect"))
    )
    (net (code "70") (name "unconnected-(P2-Pad19)") (class "Default")
      (node (ref "P2") (pin "19") (pinfunction "19_19") (pintype "passive+no_connect"))
    )
    (net (code "71") (name "unconnected-(P2-Pad20)") (class "Default")
      (node (ref "P2") (pin "20") (pinfunction "20_20") (pintype "passive+no_connect"))
    )
    (net (code "72") (name "unconnected-(P3-Pad1)") (class "Default")
      (node (ref "P3") (pin "1") (pinfunction "1_1") (pintype "passive"))
    )
    (net (code "73") (name "unconnected-(P4-Pad1)") (class "Default")
      (node (ref "P4") (pin "1") (pinfunction "1_1") (pintype "passive"))
    )
    (net (code "74") (name "unconnected-(P5-Pad1)") (class "Default")
      (node (ref "P5") (pin "1") (pinfunction "1_1") (pintype "passive"))
    )
    (net (code "75") (name "unconnected-(P8-Pad4)") (class "Default")
      (node (ref "P8") (pin "4") (pinfunction "4_4") (pintype "passive+no_connect"))
    )
    (net (code "76") (name "unconnected-(P9-Pad1)") (class "Default")
      (node (ref "P9") (pin "1") (pinfunction "1_1") (pintype "passive"))
    )
    (net (code "77") (name "unconnected-(U1-ON{slash}~{OFF}-Pad5)") (class "Default")
      (node (ref "U1") (pin "5") (pinfunction "ON/~{OFF}_5") (pintype "input+no_connect"))
    )
  )
)
